# design.net
KiCad netlist of a schematic drawn in Altium Designer
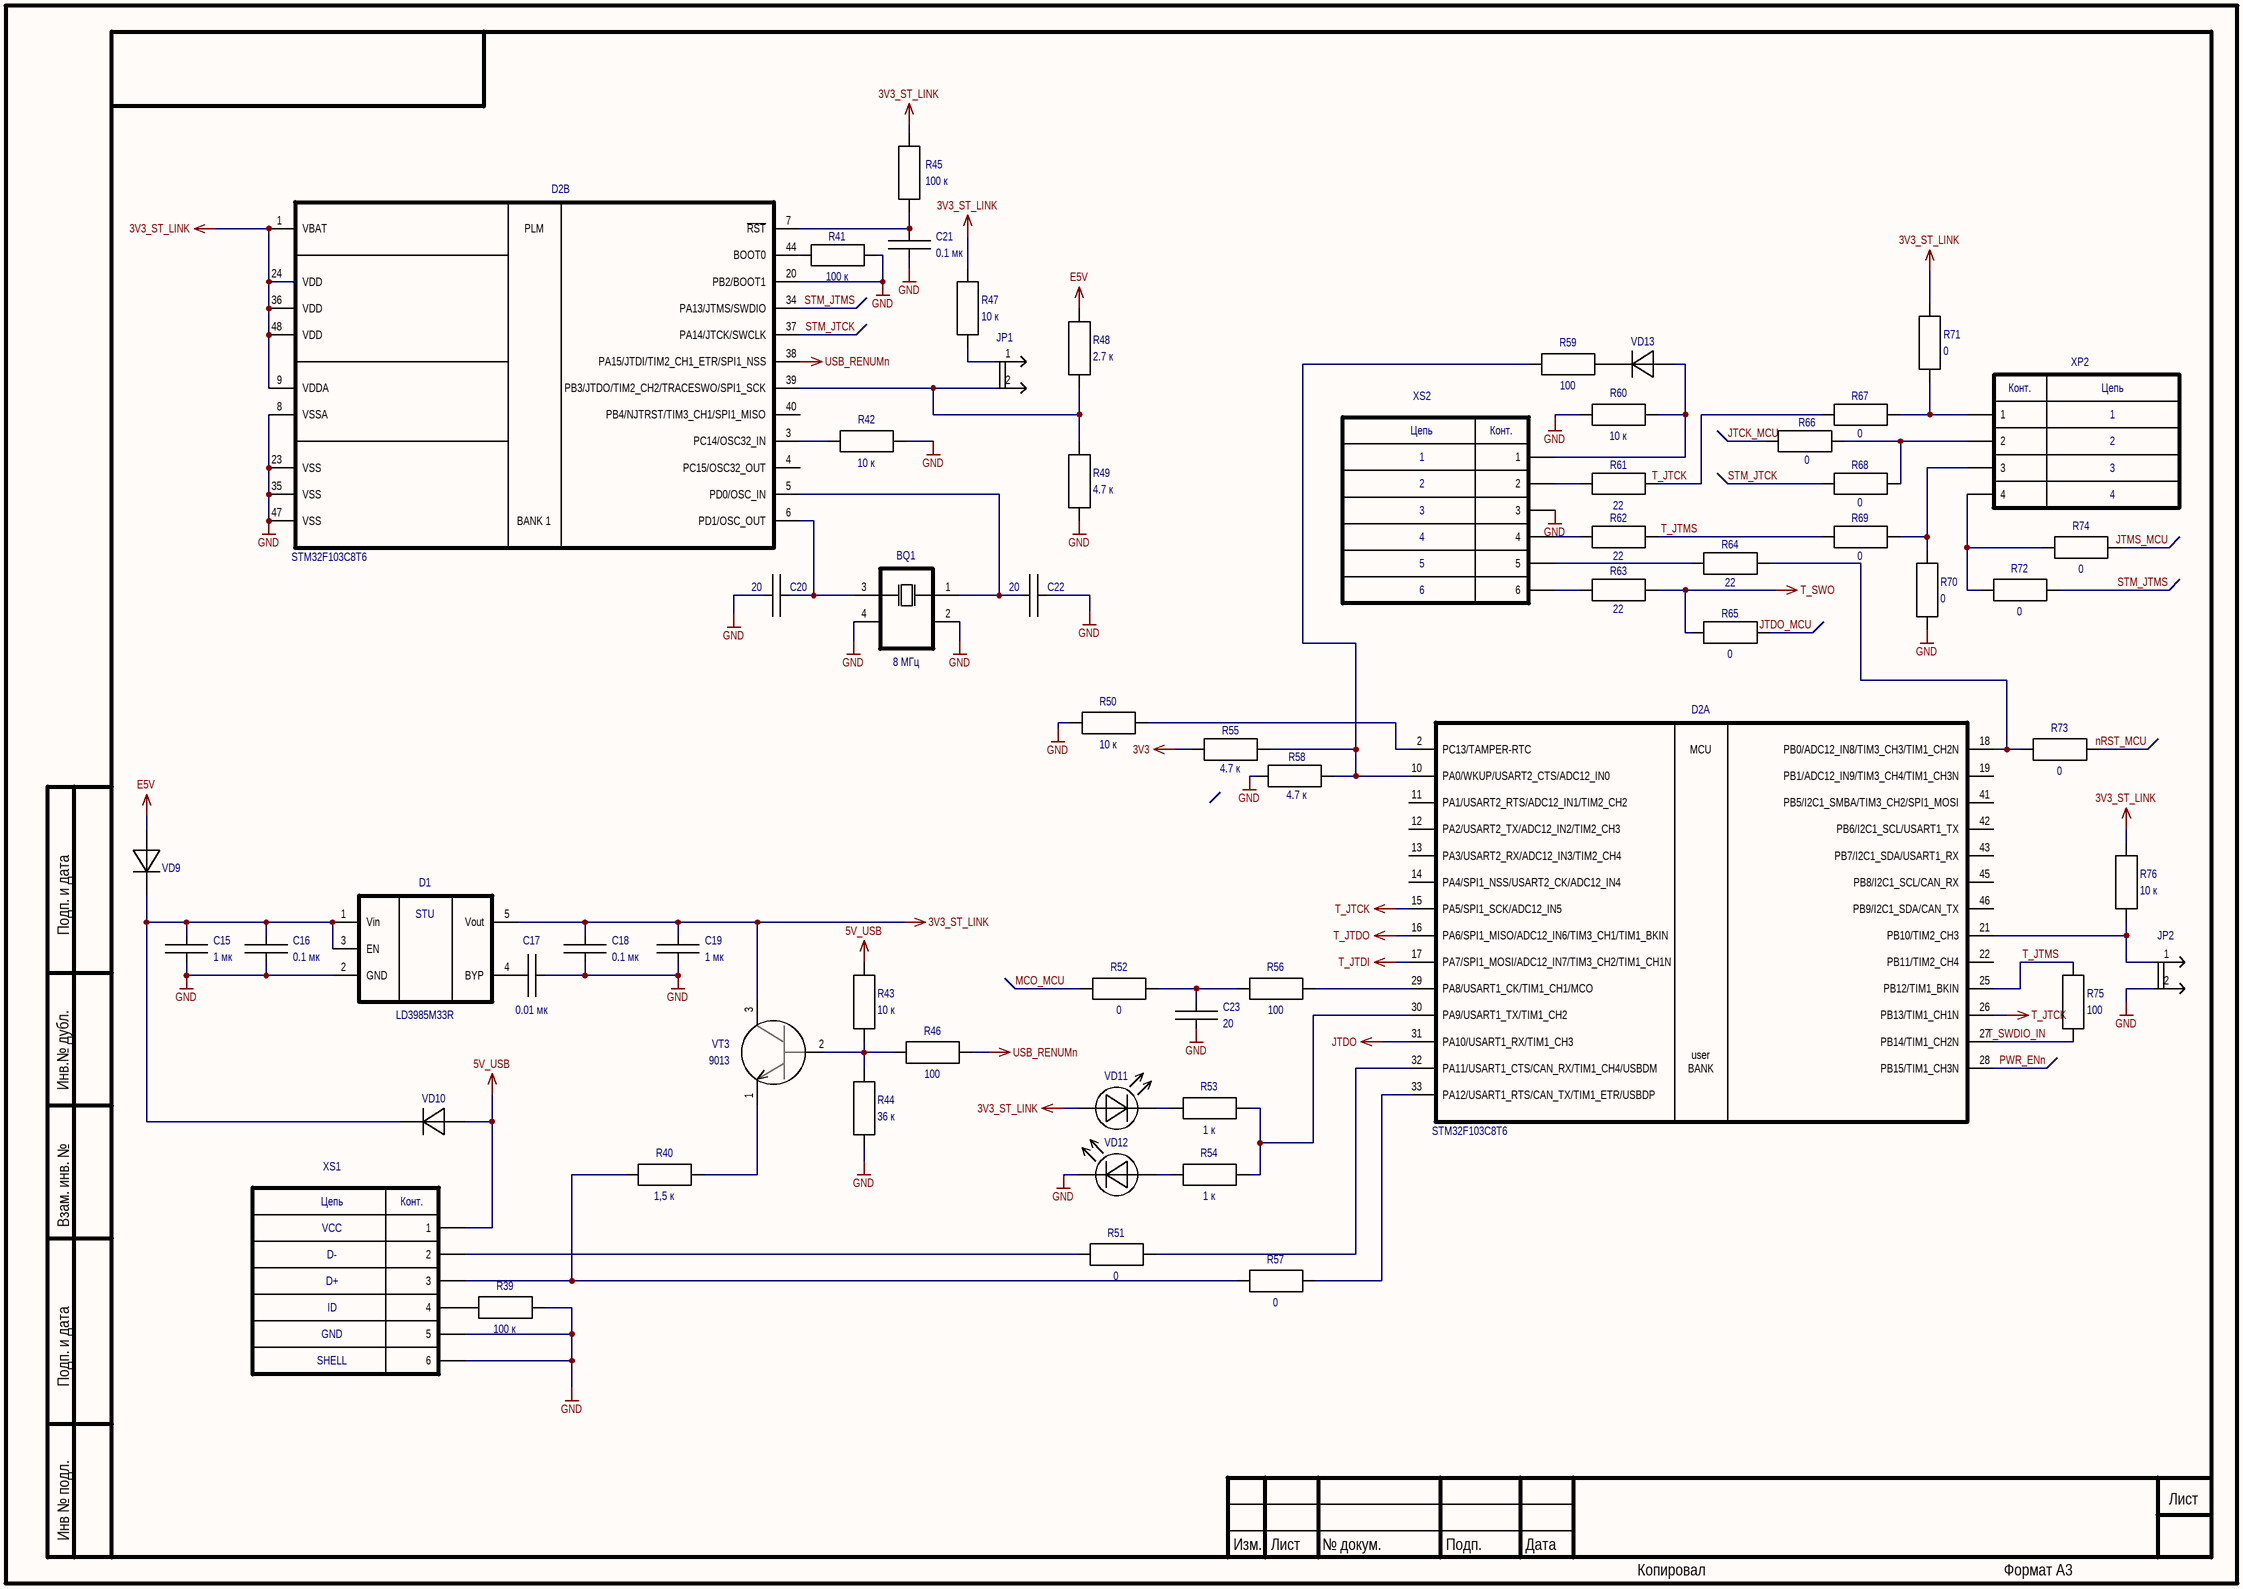
[diagram p0: программатор_мк.SchDoc]

(export (version "E")
  (design (tool "Eeschema 10.0.6"))
  (components
    (comp (ref "BQ1")
      (value "8 МГц")
      (footprint "SMD3225_4P20MHZ20PF10PPM")
      (fields (field (name "PARTNUMBER") "MQ-12.000-18") (field (name "Comment") "кварцевый резонатор_1"))
      (libsource (lib "Lisaveta_SCH") (part "кварцевый резонатор_1"))
    )
    (comp (ref "C15")
      (value "1 мк")
      (footprint "K10-79_1.6_0.8(0603)")
      (fields (field (name "Comment") "1 мкФ ±* * * *, *"))
      (libsource (lib "Lisaveta") (part "C"))
    )
    (comp (ref "C16")
      (value "0.1 мк")
      (footprint "K10-79_1.6_0.8(0603)")
      (fields (field (name "Comment") "0.1 мкФ ±* * * *, *"))
      (libsource (lib "Lisaveta") (part "C"))
    )
    (comp (ref "C17")
      (value "0.01 мк")
      (footprint "K10-79_1.6_0.8(0603)")
      (fields (field (name "Comment") "0.01 мкФ ±* * * *, *"))
      (libsource (lib "Lisaveta") (part "C"))
    )
    (comp (ref "C18")
      (value "0.1 мк")
      (footprint "K10-79_1.6_0.8(0603)")
      (fields (field (name "Comment") "0.1 мкФ ±* * * *, *"))
      (libsource (lib "Lisaveta") (part "C"))
    )
    (comp (ref "C19")
      (value "1 мк")
      (footprint "K10-79_1.6_0.8(0603)")
      (fields (field (name "Comment") "1 мкФ ±* * * *, *"))
      (libsource (lib "Lisaveta") (part "C"))
    )
    (comp (ref "C20")
      (value "20")
      (footprint "K10-79_1.6_0.8(0603)")
      (fields (field (name "Comment") "20Ф ±* * * *, *"))
      (libsource (lib "Lisaveta") (part "C"))
    )
    (comp (ref "C21")
      (value "0.1 мк")
      (footprint "K10-79_1.6_0.8(0603)")
      (fields (field (name "Comment") "0.1 мкФ ±* * * *, *"))
      (libsource (lib "Lisaveta") (part "C"))
    )
    (comp (ref "C22")
      (value "20")
      (footprint "K10-79_1.6_0.8(0603)")
      (fields (field (name "Comment") "20Ф ±* * * *, *"))
      (libsource (lib "Lisaveta") (part "C"))
    )
    (comp (ref "C23")
      (value "20")
      (footprint "K10-79_1.6_0.8(0603)")
      (fields (field (name "Comment") "20Ф ±* * * *, *"))
      (libsource (lib "Lisaveta") (part "C"))
    )
    (comp (ref "D1")
      (value "LD3985M33R")
      (footprint "SOT-23-5")
      (fields
        (field (name "PARTNUMBER") "LT1761ES5-2.5")
        (field (name "Comment") "LT1761ES5-2.5 (TSOT-23) Linear Technology")
      )
      (libsource (lib "Lisaveta") (part "LD3985M33R"))
    )
    (comp (ref "D2")
      (value "STM32F103C8T6")
      (footprint "LQFP48")
      (fields (field (name "Comment") " (LQFP-48) Xilinx"))
      (libsource (lib "Lisaveta") (part "stm32f103c8t6"))
    )
    (comp (ref "JP1") (value "* (*) *") (libsource (lib "Lisaveta") (part "JP2_vertical")))
    (comp (ref "JP2") (value "* (*) *") (libsource (lib "Lisaveta") (part "JP2_vertical")))
    (comp (ref "R39")
      (value "100 к")
      (footprint "RES 0603")
      (fields (field (name "Comment") "100 кОм ±* *, *"))
      (libsource (lib "Lisaveta") (part "R"))
    )
    (comp (ref "R40")
      (value "1,5 к")
      (footprint "RES 0603")
      (fields (field (name "Comment") "1,5 кОм ±* *, *"))
      (libsource (lib "Lisaveta") (part "R"))
    )
    (comp (ref "R41")
      (value "100 к")
      (footprint "RES 0603")
      (fields (field (name "Comment") "100 кОм ±* *, *"))
      (libsource (lib "Lisaveta") (part "R"))
    )
    (comp (ref "R42")
      (value "10 к")
      (footprint "RES 0603")
      (fields (field (name "Comment") "10 кОм ±* *, *"))
      (libsource (lib "Lisaveta") (part "R"))
    )
    (comp (ref "R43")
      (value "10 к")
      (footprint "RES 0603")
      (fields (field (name "Comment") "10 кОм ±* *, *"))
      (libsource (lib "Lisaveta") (part "R_1"))
    )
    (comp (ref "R44")
      (value "36 к")
      (footprint "RES 0603")
      (fields (field (name "Comment") "36 кОм ±* *, *"))
      (libsource (lib "Lisaveta") (part "R_1"))
    )
    (comp (ref "R45")
      (value "100 к")
      (footprint "RES 0603")
      (fields (field (name "Comment") "100 кОм ±* *, *"))
      (libsource (lib "Lisaveta") (part "R"))
    )
    (comp (ref "R46")
      (value "100")
      (footprint "RES 0603")
      (fields (field (name "Comment") "100Ом ±* *, *"))
      (libsource (lib "Lisaveta") (part "R"))
    )
    (comp (ref "R47")
      (value "10 к")
      (footprint "RES 0603")
      (fields (field (name "Comment") "10 кОм ±* *, *"))
      (libsource (lib "Lisaveta") (part "R_1"))
    )
    (comp (ref "R48")
      (value "2.7 к")
      (footprint "RES 0603")
      (fields (field (name "Comment") "2.7 кОм ±* *, *"))
      (libsource (lib "Lisaveta") (part "R_1"))
    )
    (comp (ref "R49")
      (value "4.7 к")
      (footprint "RES 0603")
      (fields (field (name "Comment") "4.7 кОм ±* *, *"))
      (libsource (lib "Lisaveta") (part "R_1"))
    )
    (comp (ref "R50")
      (value "10 к")
      (footprint "RES 0603")
      (fields (field (name "Comment") "10 кОм ±* *, *"))
      (libsource (lib "Lisaveta") (part "R"))
    )
    (comp (ref "R51")
      (value "0")
      (footprint "RES 0603")
      (fields (field (name "Comment") "0Ом ±* *, *"))
      (libsource (lib "Lisaveta") (part "R"))
    )
    (comp (ref "R52")
      (value "0")
      (footprint "RES 0603")
      (fields (field (name "Comment") "0Ом ±* *, *"))
      (libsource (lib "Lisaveta") (part "R"))
    )
    (comp (ref "R53")
      (value "1 к")
      (footprint "RES 0603")
      (fields (field (name "Comment") "1 кОм ±* *, *"))
      (libsource (lib "Lisaveta") (part "R"))
    )
    (comp (ref "R54")
      (value "1 к")
      (footprint "RES 0603")
      (fields (field (name "Comment") "1 кОм ±* *, *"))
      (libsource (lib "Lisaveta") (part "R"))
    )
    (comp (ref "R55")
      (value "4.7 к")
      (footprint "RES 0603")
      (fields (field (name "Comment") "4.7 кОм ±* *, *"))
      (libsource (lib "Lisaveta") (part "R"))
    )
    (comp (ref "R56")
      (value "100")
      (footprint "RES 0603")
      (fields (field (name "Comment") "100Ом ±* *, *"))
      (libsource (lib "Lisaveta") (part "R"))
    )
    (comp (ref "R57")
      (value "0")
      (footprint "RES 0603")
      (fields (field (name "Comment") "0Ом ±* *, *"))
      (libsource (lib "Lisaveta") (part "R"))
    )
    (comp (ref "R58")
      (value "4.7 к")
      (footprint "RES 0603")
      (fields (field (name "Comment") "4.7 кОм ±* *, *"))
      (libsource (lib "Lisaveta") (part "R"))
    )
    (comp (ref "R59")
      (value "100")
      (footprint "RES 0603")
      (fields (field (name "Comment") "100Ом ±* *, *"))
      (libsource (lib "Lisaveta") (part "R"))
    )
    (comp (ref "R60")
      (value "10 к")
      (footprint "RES 0603")
      (fields (field (name "Comment") "10 кОм ±* *, *"))
      (libsource (lib "Lisaveta") (part "R"))
    )
    (comp (ref "R61")
      (value "22")
      (footprint "RES 0603")
      (fields (field (name "Comment") "22Ом ±* *, *"))
      (libsource (lib "Lisaveta") (part "R"))
    )
    (comp (ref "R62")
      (value "22")
      (footprint "RES 0603")
      (fields (field (name "Comment") "22Ом ±* *, *"))
      (libsource (lib "Lisaveta") (part "R"))
    )
    (comp (ref "R63")
      (value "22")
      (footprint "RES 0603")
      (fields (field (name "Comment") "22Ом ±* *, *"))
      (libsource (lib "Lisaveta") (part "R"))
    )
    (comp (ref "R64")
      (value "22")
      (footprint "RES 0603")
      (fields (field (name "Comment") "22Ом ±* *, *"))
      (libsource (lib "Lisaveta") (part "R"))
    )
    (comp (ref "R65")
      (value "0")
      (footprint "RES 0603")
      (fields (field (name "Comment") "0Ом ±* *, *"))
      (libsource (lib "Lisaveta") (part "R"))
    )
    (comp (ref "R66")
      (value "0")
      (footprint "RES 0603")
      (fields (field (name "Comment") "0Ом ±* *, *"))
      (libsource (lib "Lisaveta") (part "R"))
    )
    (comp (ref "R67")
      (value "0")
      (footprint "RES 0603")
      (fields (field (name "Comment") "0Ом ±* *, *"))
      (libsource (lib "Lisaveta") (part "R"))
    )
    (comp (ref "R68")
      (value "0")
      (footprint "RES 0603")
      (fields (field (name "Comment") "0Ом ±* *, *"))
      (libsource (lib "Lisaveta") (part "R"))
    )
    (comp (ref "R69")
      (value "0")
      (footprint "RES 0603")
      (fields (field (name "Comment") "0Ом ±* *, *"))
      (libsource (lib "Lisaveta") (part "R"))
    )
    (comp (ref "R70")
      (value "0")
      (footprint "RES 0603")
      (fields (field (name "Comment") "0Ом ±* *, *"))
      (libsource (lib "Lisaveta") (part "R_1"))
    )
    (comp (ref "R71")
      (value "0")
      (footprint "RES 0603")
      (fields (field (name "Comment") "0Ом ±* *, *"))
      (libsource (lib "Lisaveta") (part "R_1"))
    )
    (comp (ref "R72")
      (value "0")
      (footprint "RES 0603")
      (fields (field (name "Comment") "0Ом ±* *, *"))
      (libsource (lib "Lisaveta") (part "R"))
    )
    (comp (ref "R73")
      (value "0")
      (footprint "RES 0603")
      (fields (field (name "Comment") "0Ом ±* *, *"))
      (libsource (lib "Lisaveta") (part "R"))
    )
    (comp (ref "R74")
      (value "0")
      (footprint "RES 0603")
      (fields (field (name "Comment") "0Ом ±* *, *"))
      (libsource (lib "Lisaveta") (part "R"))
    )
    (comp (ref "R75")
      (value "100")
      (footprint "RES 0603")
      (fields (field (name "Comment") "100Ом ±* *, *"))
      (libsource (lib "Lisaveta") (part "R_1"))
    )
    (comp (ref "R76")
      (value "10 к")
      (footprint "RES 0603")
      (fields (field (name "Comment") "10 кОм ±* *, *"))
      (libsource (lib "Lisaveta") (part "R_1"))
    )
    (comp (ref "VD9") (value "BAS316") (footprint "SOD-323") (libsource (lib "Lisaveta") (part "BAS316")))
    (comp (ref "VD10") (value "BAS316") (footprint "SOD323") (libsource (lib "Lisaveta") (part "BAS316")))
    (comp (ref "VD11")
      (value "Светодиод")
      (footprint "LED 0603")
      (libsource (lib "Lisaveta") (part "Светодиод"))
    )
    (comp (ref "VD12")
      (value "Светодиод")
      (footprint "LED 0603")
      (libsource (lib "Lisaveta") (part "Светодиод"))
    )
    (comp (ref "VD13") (value "BAS316") (footprint "SOD-323") (libsource (lib "Lisaveta") (part "BAS316")))
    (comp (ref "VT3")
      (value "9013")
      (footprint "SOT23(KT-46)")
      (fields (field (name "PARTNUMBER") "BC847C") (field (name "Comment") "BC847C (SOT-23) NXP"))
      (libsource (lib "Lisaveta") (part "T!9013"))
    )
    (comp (ref "XP2")
      (value "KONT_POLE_4")
      (footprint "PLS-4")
      (fields (field (name "1") "1") (field (name "2") "2") (field (name "3") "3") (field (name "4") "4"))
      (libsource (lib "Lisaveta") (part "KONT_POLE_4"))
    )
    (comp (ref "XS1")
      (value "KONT_POLE_USB_DBG")
      (footprint "MICRO_USB")
      (fields
        (field (name "1") "VCC")
        (field (name "3") "D+")
        (field (name "2") "D-")
        (field (name "4") "ID")
        (field (name "6") "SHELL")
        (field (name "5") "GND")
      )
      (libsource (lib "Lisaveta") (part "KONT_POLE_USB_DBG"))
    )
    (comp (ref "XS2")
      (value "KONT_POLE_USB_DBG")
      (footprint "PBS-6")
      (fields
        (field (name "1") "1")
        (field (name "3") "3")
        (field (name "2") "2")
        (field (name "4") "4")
        (field (name "6") "6")
        (field (name "5") "5")
      )
      (libsource (lib "Lisaveta") (part "KONT_POLE_USB_DBG"))
    )
  )
  (nets
    (net (code "1") (name "/JTCK_MCU") (class "Default")
      (node (ref "R66") (pin "1") (pinfunction "1_1") (pintype "passive"))
    )
    (net (code "2") (name "/JTDO_MCU") (class "Default")
      (node (ref "R65") (pin "2") (pinfunction "2_2") (pintype "passive"))
    )
    (net (code "3") (name "/JTMS_MCU") (class "Default")
      (node (ref "R74") (pin "1") (pinfunction "1_1") (pintype "passive"))
    )
    (net (code "4") (name "/MCO_MCU") (class "Default")
      (node (ref "R52") (pin "1") (pinfunction "1_1") (pintype "passive"))
    )
    (net (code "5") (name "/PWR_ENn") (class "Default")
      (node (ref "D2") (pin "28") (pinfunction "PB15/TIM1_CH3N_28") (pintype "passive"))
    )
    (net (code "6") (name "/STM_JTCK") (class "Default")
      (node (ref "D2") (pin "37") (pinfunction "PA14/JTCK/SWCLK_37") (pintype "passive"))
      (node (ref "R68") (pin "2") (pinfunction "2_2") (pintype "passive"))
    )
    (net (code "7") (name "/STM_JTMS") (class "Default")
      (node (ref "D2") (pin "34") (pinfunction "PA13/JTMS/SWDIO_34") (pintype "passive"))
      (node (ref "R72") (pin "1") (pinfunction "1_1") (pintype "passive"))
    )
    (net (code "8") (name "/T_JTMS") (class "Default")
      (node (ref "D2") (pin "25") (pinfunction "PB12/TIM1_BKIN_25") (pintype "passive"))
      (node (ref "R62") (pin "2") (pinfunction "2_2") (pintype "passive"))
      (node (ref "R69") (pin "1") (pinfunction "1_1") (pintype "passive"))
      (node (ref "R75") (pin "1") (pinfunction "1_1") (pintype "passive"))
    )
    (net (code "9") (name "/T_SWDIO_IN") (class "Default")
      (node (ref "D2") (pin "27") (pinfunction "PB14/TIM1_CH2N_27") (pintype "passive"))
      (node (ref "R75") (pin "2") (pinfunction "2_2") (pintype "passive"))
    )
    (net (code "10") (name "/nRST_MCU") (class "Default")
      (node (ref "R73") (pin "2") (pinfunction "2_2") (pintype "passive"))
    )
    (net (code "11") (name "3V3") (class "Default")
      (node (ref "R55") (pin "1") (pinfunction "1_1") (pintype "passive"))
    )
    (net (code "12") (name "3V3_ST_LINK") (class "Default")
      (node (ref "C18") (pin "2") (pinfunction "2_2") (pintype "passive"))
      (node (ref "C19") (pin "2") (pinfunction "2_2") (pintype "passive"))
      (node (ref "D1") (pin "5") (pinfunction "Vout_5") (pintype "passive"))
      (node (ref "D2") (pin "1") (pinfunction "VBAT_1") (pintype "passive"))
      (node (ref "D2") (pin "24") (pinfunction "VDD_24") (pintype "passive"))
      (node (ref "D2") (pin "36") (pinfunction "VDD_36") (pintype "passive"))
      (node (ref "D2") (pin "48") (pinfunction "VDD_48") (pintype "passive"))
      (node (ref "D2") (pin "9") (pinfunction "VDDA_9") (pintype "passive"))
      (node (ref "R45") (pin "2") (pinfunction "2_2") (pintype "passive"))
      (node (ref "R47") (pin "1") (pinfunction "1_1") (pintype "passive"))
      (node (ref "R71") (pin "1") (pinfunction "1_1") (pintype "passive"))
      (node (ref "R76") (pin "1") (pinfunction "1_1") (pintype "passive"))
      (node (ref "VD11") (pin "1") (pinfunction "A_1") (pintype "passive"))
      (node (ref "VT3") (pin "3") (pinfunction "3_3") (pintype "passive"))
    )
    (net (code "13") (name "5V_USB") (class "Default")
      (node (ref "R43") (pin "1") (pinfunction "1_1") (pintype "passive"))
      (node (ref "VD10") (pin "1") (pinfunction "1_1") (pintype "passive"))
      (node (ref "XS1") (pin "1") (pinfunction "1_1") (pintype "passive"))
    )
    (net (code "14") (name "E5V") (class "Default")
      (node (ref "R48") (pin "1") (pinfunction "1_1") (pintype "passive"))
      (node (ref "VD9") (pin "1") (pinfunction "1_1") (pintype "passive"))
    )
    (net (code "15") (name "GND") (class "Default")
      (node (ref "BQ1") (pin "2") (pinfunction "GND_2") (pintype "passive"))
      (node (ref "BQ1") (pin "4") (pinfunction "GND_4") (pintype "passive"))
      (node (ref "C15") (pin "1") (pinfunction "1_1") (pintype "passive"))
      (node (ref "C16") (pin "1") (pinfunction "1_1") (pintype "passive"))
      (node (ref "C17") (pin "1") (pinfunction "1_1") (pintype "passive"))
      (node (ref "C18") (pin "1") (pinfunction "1_1") (pintype "passive"))
      (node (ref "C19") (pin "1") (pinfunction "1_1") (pintype "passive"))
      (node (ref "C20") (pin "2") (pinfunction "2_2") (pintype "passive"))
      (node (ref "C21") (pin "1") (pinfunction "1_1") (pintype "passive"))
      (node (ref "C22") (pin "1") (pinfunction "1_1") (pintype "passive"))
      (node (ref "C23") (pin "2") (pinfunction "2_2") (pintype "passive"))
      (node (ref "D1") (pin "2") (pinfunction "GND_2") (pintype "passive"))
      (node (ref "D2") (pin "20") (pinfunction "PB2/BOOT1_20") (pintype "passive"))
      (node (ref "D2") (pin "23") (pinfunction "VSS_23") (pintype "passive"))
      (node (ref "D2") (pin "35") (pinfunction "VSS_35") (pintype "passive"))
      (node (ref "D2") (pin "47") (pinfunction "VSS_47") (pintype "passive"))
      (node (ref "D2") (pin "8") (pinfunction "VSSA_8") (pintype "passive"))
      (node (ref "JP2") (pin "2") (pinfunction "2_2") (pintype "passive"))
      (node (ref "R39") (pin "2") (pinfunction "2_2") (pintype "passive"))
      (node (ref "R41") (pin "2") (pinfunction "2_2") (pintype "passive"))
      (node (ref "R42") (pin "1") (pinfunction "1_1") (pintype "passive"))
      (node (ref "R44") (pin "2") (pinfunction "2_2") (pintype "passive"))
      (node (ref "R49") (pin "2") (pinfunction "2_2") (pintype "passive"))
      (node (ref "R50") (pin "1") (pinfunction "1_1") (pintype "passive"))
      (node (ref "R58") (pin "1") (pinfunction "1_1") (pintype "passive"))
      (node (ref "R60") (pin "2") (pinfunction "2_2") (pintype "passive"))
      (node (ref "R70") (pin "2") (pinfunction "2_2") (pintype "passive"))
      (node (ref "VD12") (pin "2") (pinfunction "C_2") (pintype "passive"))
      (node (ref "XS1") (pin "5") (pinfunction "5_5") (pintype "passive"))
      (node (ref "XS1") (pin "6") (pinfunction "6_6") (pintype "passive"))
      (node (ref "XS2") (pin "3") (pinfunction "3_3") (pintype "passive"))
    )
    (net (code "16") (name "JTDO") (class "Default")
      (node (ref "D2") (pin "31") (pinfunction "PA10/USART1_RX/TIM1_CH3_31") (pintype "passive"))
    )
    (net (code "17") (name "Net-(C23-Pad1)") (class "Default")
      (node (ref "C23") (pin "1") (pinfunction "1_1") (pintype "passive"))
      (node (ref "R52") (pin "2") (pinfunction "2_2") (pintype "passive"))
      (node (ref "R56") (pin "1") (pinfunction "1_1") (pintype "passive"))
    )
    (net (code "18") (name "Net-(D1-BYP)") (class "Default")
      (node (ref "C17") (pin "2") (pinfunction "2_2") (pintype "passive"))
      (node (ref "D1") (pin "4") (pinfunction "BYP_4") (pintype "passive"))
    )
    (net (code "19") (name "Net-(D1-EN)") (class "Default")
      (node (ref "C15") (pin "2") (pinfunction "2_2") (pintype "passive"))
      (node (ref "C16") (pin "2") (pinfunction "2_2") (pintype "passive"))
      (node (ref "D1") (pin "1") (pinfunction "Vin_1") (pintype "passive"))
      (node (ref "D1") (pin "3") (pinfunction "EN_3") (pintype "passive"))
      (node (ref "VD10") (pin "2") (pinfunction "2_2") (pintype "passive"))
      (node (ref "VD9") (pin "2") (pinfunction "2_2") (pintype "passive"))
    )
    (net (code "20") (name "Net-(D2A-PA0{slash}WKUP{slash}USART2_CTS{slash}ADC12_IN0)") (class "Default")
      (node (ref "D2") (pin "10") (pinfunction "PA0/WKUP/USART2_CTS/ADC12_IN0_10") (pintype "passive"))
      (node (ref "R55") (pin "2") (pinfunction "2_2") (pintype "passive"))
      (node (ref "R58") (pin "2") (pinfunction "2_2") (pintype "passive"))
      (node (ref "R59") (pin "2") (pinfunction "2_2") (pintype "passive"))
    )
    (net (code "21") (name "Net-(D2A-PA8{slash}USART1_CK{slash}TIM1_CH1{slash}MCO)") (class "Default")
      (node (ref "D2") (pin "29") (pinfunction "PA8/USART1_CK/TIM1_CH1/MCO_29") (pintype "passive"))
      (node (ref "R56") (pin "2") (pinfunction "2_2") (pintype "passive"))
    )
    (net (code "22") (name "Net-(D2A-PA9{slash}USART1_TX{slash}TIM1_CH2)") (class "Default")
      (node (ref "D2") (pin "30") (pinfunction "PA9/USART1_TX/TIM1_CH2_30") (pintype "passive"))
      (node (ref "R53") (pin "2") (pinfunction "2_2") (pintype "passive"))
      (node (ref "R54") (pin "2") (pinfunction "2_2") (pintype "passive"))
    )
    (net (code "23") (name "Net-(D2A-PA11{slash}USART1_CTS{slash}CAN_RX{slash}TIM1_CH4{slash}USBDM)") (class "Default")
      (node (ref "D2") (pin "32") (pinfunction "PA11/USART1_CTS/CAN_RX/TIM1_CH4/USBDM_32") (pintype "passive"))
      (node (ref "R51") (pin "2") (pinfunction "2_2") (pintype "passive"))
    )
    (net (code "24") (name "Net-(D2A-PA12{slash}USART1_RTS{slash}CAN_TX{slash}TIM1_ETR{slash}USBDP)") (class "Default")
      (node (ref "D2") (pin "33") (pinfunction "PA12/USART1_RTS/CAN_TX/TIM1_ETR/USBDP_33") (pintype "passive"))
      (node (ref "R57") (pin "2") (pinfunction "2_2") (pintype "passive"))
    )
    (net (code "25") (name "Net-(D2A-PB0{slash}ADC12_IN8{slash}TIM3_CH3{slash}TIM1_CH2N)") (class "Default")
      (node (ref "D2") (pin "18") (pinfunction "PB0/ADC12_IN8/TIM3_CH3/TIM1_CH2N_18") (pintype "passive"))
      (node (ref "R64") (pin "2") (pinfunction "2_2") (pintype "passive"))
      (node (ref "R73") (pin "1") (pinfunction "1_1") (pintype "passive"))
    )
    (net (code "26") (name "Net-(D2A-PB10{slash}TIM2_CH3)") (class "Default")
      (node (ref "D2") (pin "21") (pinfunction "PB10/TIM2_CH3_21") (pintype "passive"))
      (node (ref "JP2") (pin "1") (pinfunction "1_1") (pintype "passive"))
      (node (ref "R76") (pin "2") (pinfunction "2_2") (pintype "passive"))
    )
    (net (code "27") (name "Net-(D2A-PC13{slash}TAMPER-RTC)") (class "Default")
      (node (ref "D2") (pin "2") (pinfunction "PC13/TAMPER-RTC_2") (pintype "passive"))
      (node (ref "R50") (pin "2") (pinfunction "2_2") (pintype "passive"))
    )
    (net (code "28") (name "Net-(D2B-BOOT0)") (class "Default")
      (node (ref "D2") (pin "44") (pinfunction "BOOT0_44") (pintype "passive"))
      (node (ref "R41") (pin "1") (pinfunction "1_1") (pintype "passive"))
    )
    (net (code "29") (name "Net-(D2B-PB3{slash}JTDO{slash}TIM2_CH2{slash}TRACESWO{slash}SPI1_SCK)") (class "Default")
      (node (ref "D2") (pin "39") (pinfunction "PB3/JTDO/TIM2_CH2/TRACESWO/SPI1_SCK_39") (pintype "passive"))
      (node (ref "JP1") (pin "2") (pinfunction "2_2") (pintype "passive"))
      (node (ref "R48") (pin "2") (pinfunction "2_2") (pintype "passive"))
      (node (ref "R49") (pin "1") (pinfunction "1_1") (pintype "passive"))
    )
    (net (code "30") (name "Net-(D2B-PC14{slash}OSC32_IN)") (class "Default")
      (node (ref "D2") (pin "3") (pinfunction "PC14/OSC32_IN_3") (pintype "passive"))
      (node (ref "R42") (pin "2") (pinfunction "2_2") (pintype "passive"))
    )
    (net (code "31") (name "Net-(D2B-PD0{slash}OSC_IN)") (class "Default")
      (node (ref "BQ1") (pin "1") (pinfunction "1_1") (pintype "passive"))
      (node (ref "C22") (pin "2") (pinfunction "2_2") (pintype "passive"))
      (node (ref "D2") (pin "5") (pinfunction "PD0/OSC_IN_5") (pintype "passive"))
    )
    (net (code "32") (name "Net-(D2B-PD1{slash}OSC_OUT)") (class "Default")
      (node (ref "BQ1") (pin "3") (pinfunction "3_3") (pintype "passive"))
      (node (ref "C20") (pin "1") (pinfunction "1_1") (pintype "passive"))
      (node (ref "D2") (pin "6") (pinfunction "PD1/OSC_OUT_6") (pintype "passive"))
    )
    (net (code "33") (name "Net-(D2B-~{RST})") (class "Default")
      (node (ref "C21") (pin "2") (pinfunction "2_2") (pintype "passive"))
      (node (ref "D2") (pin "7") (pinfunction "~{RST}_7") (pintype "passive"))
      (node (ref "R45") (pin "1") (pinfunction "1_1") (pintype "passive"))
    )
    (net (code "34") (name "Net-(JP1-Pad1)") (class "Default")
      (node (ref "JP1") (pin "1") (pinfunction "1_1") (pintype "passive"))
      (node (ref "R47") (pin "2") (pinfunction "2_2") (pintype "passive"))
    )
    (net (code "35") (name "Net-(R39-Pad1)") (class "Default")
      (node (ref "R39") (pin "1") (pinfunction "1_1") (pintype "passive"))
      (node (ref "XS1") (pin "4") (pinfunction "4_4") (pintype "passive"))
    )
    (net (code "36") (name "Net-(R40-Pad1)") (class "Default")
      (node (ref "R40") (pin "1") (pinfunction "1_1") (pintype "passive"))
      (node (ref "R57") (pin "1") (pinfunction "1_1") (pintype "passive"))
      (node (ref "XS1") (pin "3") (pinfunction "3_3") (pintype "passive"))
    )
    (net (code "37") (name "Net-(R40-Pad2)") (class "Default")
      (node (ref "R40") (pin "2") (pinfunction "2_2") (pintype "passive"))
      (node (ref "VT3") (pin "1") (pinfunction "1_1") (pintype "passive"))
    )
    (net (code "38") (name "Net-(R43-Pad2)") (class "Default")
      (node (ref "R43") (pin "2") (pinfunction "2_2") (pintype "passive"))
      (node (ref "R44") (pin "1") (pinfunction "1_1") (pintype "passive"))
      (node (ref "R46") (pin "1") (pinfunction "1_1") (pintype "passive"))
      (node (ref "VT3") (pin "2") (pinfunction "2_2") (pintype "passive"))
    )
    (net (code "39") (name "Net-(R51-Pad1)") (class "Default")
      (node (ref "R51") (pin "1") (pinfunction "1_1") (pintype "passive"))
      (node (ref "XS1") (pin "2") (pinfunction "2_2") (pintype "passive"))
    )
    (net (code "40") (name "Net-(R59-Pad1)") (class "Default")
      (node (ref "R59") (pin "1") (pinfunction "1_1") (pintype "passive"))
      (node (ref "VD13") (pin "2") (pinfunction "2_2") (pintype "passive"))
    )
    (net (code "41") (name "Net-(R60-Pad1)") (class "Default")
      (node (ref "R60") (pin "1") (pinfunction "1_1") (pintype "passive"))
      (node (ref "VD13") (pin "1") (pinfunction "1_1") (pintype "passive"))
      (node (ref "XS2") (pin "1") (pinfunction "1_1") (pintype "passive"))
    )
    (net (code "42") (name "Net-(R61-Pad1)") (class "Default")
      (node (ref "R61") (pin "1") (pinfunction "1_1") (pintype "passive"))
      (node (ref "XS2") (pin "2") (pinfunction "2_2") (pintype "passive"))
    )
    (net (code "43") (name "Net-(R62-Pad1)") (class "Default")
      (node (ref "R62") (pin "1") (pinfunction "1_1") (pintype "passive"))
      (node (ref "XS2") (pin "4") (pinfunction "4_4") (pintype "passive"))
    )
    (net (code "44") (name "Net-(R63-Pad1)") (class "Default")
      (node (ref "R63") (pin "1") (pinfunction "1_1") (pintype "passive"))
      (node (ref "XS2") (pin "6") (pinfunction "6_6") (pintype "passive"))
    )
    (net (code "45") (name "Net-(R64-Pad1)") (class "Default")
      (node (ref "R64") (pin "1") (pinfunction "1_1") (pintype "passive"))
      (node (ref "XS2") (pin "5") (pinfunction "5_5") (pintype "passive"))
    )
    (net (code "46") (name "Net-(R66-Pad2)") (class "Default")
      (node (ref "R66") (pin "2") (pinfunction "2_2") (pintype "passive"))
      (node (ref "R68") (pin "1") (pinfunction "1_1") (pintype "passive"))
      (node (ref "XP2") (pin "2") (pinfunction "2_2") (pintype "passive"))
    )
    (net (code "47") (name "Net-(R67-Pad1)") (class "Default")
      (node (ref "R67") (pin "1") (pinfunction "1_1") (pintype "passive"))
      (node (ref "R71") (pin "2") (pinfunction "2_2") (pintype "passive"))
      (node (ref "XP2") (pin "1") (pinfunction "1_1") (pintype "passive"))
    )
    (net (code "48") (name "Net-(R69-Pad2)") (class "Default")
      (node (ref "R69") (pin "2") (pinfunction "2_2") (pintype "passive"))
      (node (ref "R70") (pin "1") (pinfunction "1_1") (pintype "passive"))
      (node (ref "XP2") (pin "3") (pinfunction "3_3") (pintype "passive"))
    )
    (net (code "49") (name "Net-(R72-Pad2)") (class "Default")
      (node (ref "R72") (pin "2") (pinfunction "2_2") (pintype "passive"))
      (node (ref "R74") (pin "2") (pinfunction "2_2") (pintype "passive"))
      (node (ref "XP2") (pin "4") (pinfunction "4_4") (pintype "passive"))
    )
    (net (code "50") (name "Net-(VD11-C)") (class "Default")
      (node (ref "R53") (pin "1") (pinfunction "1_1") (pintype "passive"))
      (node (ref "VD11") (pin "2") (pinfunction "C_2") (pintype "passive"))
    )
    (net (code "51") (name "Net-(VD12-A)") (class "Default")
      (node (ref "R54") (pin "1") (pinfunction "1_1") (pintype "passive"))
      (node (ref "VD12") (pin "1") (pinfunction "A_1") (pintype "passive"))
    )
    (net (code "52") (name "T_JTCK") (class "Default")
      (node (ref "D2") (pin "15") (pinfunction "PA5/SPI1_SCK/ADC12_IN5_15") (pintype "passive"))
      (node (ref "D2") (pin "26") (pinfunction "PB13/TIM1_CH1N_26") (pintype "passive"))
      (node (ref "R61") (pin "2") (pinfunction "2_2") (pintype "passive"))
      (node (ref "R67") (pin "2") (pinfunction "2_2") (pintype "passive"))
    )
    (net (code "53") (name "T_JTDI") (class "Default")
      (node (ref "D2") (pin "17") (pinfunction "PA7/SPI1_MOSI/ADC12_IN7/TIM3_CH2/TIM1_CH1N_17") (pintype "passive"))
    )
    (net (code "54") (name "T_JTDO") (class "Default")
      (node (ref "D2") (pin "16") (pinfunction "PA6/SPI1_MISO/ADC12_IN6/TIM3_CH1/TIM1_BKIN_16") (pintype "passive"))
    )
    (net (code "55") (name "T_SWO") (class "Default")
      (node (ref "R63") (pin "2") (pinfunction "2_2") (pintype "passive"))
      (node (ref "R65") (pin "1") (pinfunction "1_1") (pintype "passive"))
    )
    (net (code "56") (name "USB_RENUMn") (class "Default")
      (node (ref "D2") (pin "38") (pinfunction "PA15/JTDI/TIM2_CH1_ETR/SPI1_NSS_38") (pintype "passive"))
      (node (ref "R46") (pin "2") (pinfunction "2_2") (pintype "passive"))
    )
    (net (code "57") (name "unconnected-(D2A-PA1{slash}USART2_RTS{slash}ADC12_IN1{slash}TIM2_CH2-Pad11)") (class "Default")
      (node (ref "D2") (pin "11") (pinfunction "PA1/USART2_RTS/ADC12_IN1/TIM2_CH2_11") (pintype "passive"))
    )
    (net (code "58") (name "unconnected-(D2A-PA2{slash}USART2_TX{slash}ADC12_IN2{slash}TIM2_CH3-Pad12)") (class "Default")
      (node (ref "D2") (pin "12") (pinfunction "PA2/USART2_TX/ADC12_IN2/TIM2_CH3_12") (pintype "passive"))
    )
    (net (code "59") (name "unconnected-(D2A-PA3{slash}USART2_RX{slash}ADC12_IN3{slash}TIM2_CH4-Pad13)") (class "Default")
      (node (ref "D2") (pin "13") (pinfunction "PA3/USART2_RX/ADC12_IN3/TIM2_CH4_13") (pintype "passive"))
    )
    (net (code "60") (name "unconnected-(D2A-PA4{slash}SPI1_NSS{slash}USART2_CK{slash}ADC12_IN4-Pad14)") (class "Default")
      (node (ref "D2") (pin "14") (pinfunction "PA4/SPI1_NSS/USART2_CK/ADC12_IN4_14") (pintype "passive"))
    )
    (net (code "61") (name "unconnected-(D2A-PB1{slash}ADC12_IN9{slash}TIM3_CH4{slash}TIM1_CH3N-Pad19)") (class "Default")
      (node (ref "D2") (pin "19") (pinfunction "PB1/ADC12_IN9/TIM3_CH4/TIM1_CH3N_19") (pintype "passive"))
    )
    (net (code "62") (name "unconnected-(D2A-PB5{slash}I2C1_SMBA{slash}TIM3_CH2{slash}SPI1_MOSI-Pad41)") (class "Default")
      (node (ref "D2") (pin "41") (pinfunction "PB5/I2C1_SMBA/TIM3_CH2/SPI1_MOSI_41") (pintype "passive"))
    )
    (net (code "63") (name "unconnected-(D2A-PB6{slash}I2C1_SCL{slash}USART1_TX-Pad42)") (class "Default")
      (node (ref "D2") (pin "42") (pinfunction "PB6/I2C1_SCL/USART1_TX_42") (pintype "passive"))
    )
    (net (code "64") (name "unconnected-(D2A-PB7{slash}I2C1_SDA{slash}USART1_RX-Pad43)") (class "Default")
      (node (ref "D2") (pin "43") (pinfunction "PB7/I2C1_SDA/USART1_RX_43") (pintype "passive"))
    )
    (net (code "65") (name "unconnected-(D2A-PB8{slash}I2C1_SCL{slash}CAN_RX-Pad45)") (class "Default")
      (node (ref "D2") (pin "45") (pinfunction "PB8/I2C1_SCL/CAN_RX_45") (pintype "passive"))
    )
    (net (code "66") (name "unconnected-(D2A-PB9{slash}I2C1_SDA{slash}CAN_TX-Pad46)") (class "Default")
      (node (ref "D2") (pin "46") (pinfunction "PB9/I2C1_SDA/CAN_TX_46") (pintype "passive"))
    )
    (net (code "67") (name "unconnected-(D2A-PB11{slash}TIM2_CH4-Pad22)") (class "Default")
      (node (ref "D2") (pin "22") (pinfunction "PB11/TIM2_CH4_22") (pintype "passive"))
    )
    (net (code "68") (name "unconnected-(D2B-PB4{slash}NJTRST{slash}TIM3_CH1{slash}SPI1_MISO-Pad40)") (class "Default")
      (node (ref "D2") (pin "40") (pinfunction "PB4/NJTRST/TIM3_CH1/SPI1_MISO_40") (pintype "passive"))
    )
    (net (code "69") (name "unconnected-(D2B-PC15{slash}OSC32_OUT-Pad4)") (class "Default")
      (node (ref "D2") (pin "4") (pinfunction "PC15/OSC32_OUT_4") (pintype "passive"))
    )
  )
)
